# Board1.net
KiCad netlist of a schematic drawn in Altium Designer
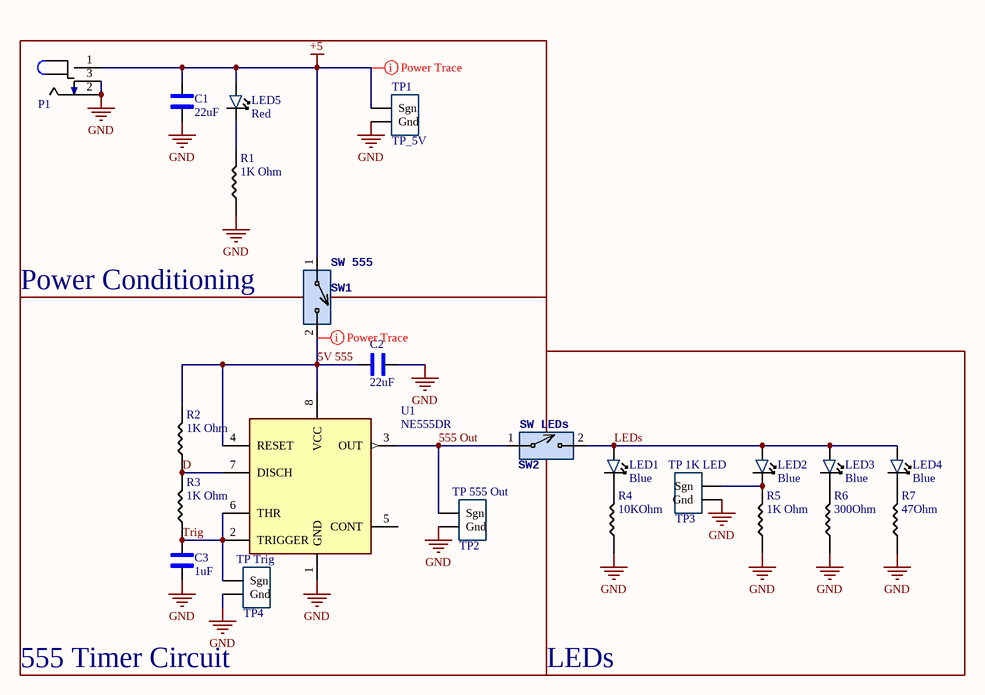
[diagram p0: Board1.SchDoc]

(export (version "E")
  (design (tool "Eeschema 10.0.6"))
  (components
    (comp (ref "C1")
      (value "22uF")
      (footprint "1206_Passive_Capacitor")
      (description "22uF ±10% 25V X5R 1206 Multilayer Ceramic Capacitors MLCC - SMD/SMT RoHS")
      (fields (field (name "MFR PART #") "CL31A226KAHNNNE") (field (name "LCSC PART#") "C12891"))
      (libsource (lib "ECEN5730Lib_2023_01_DS") (part "C_22uF_1206"))
    )
    (comp (ref "C2")
      (value "22uF")
      (footprint "1206_Passive_Capacitor")
      (description "22uF ±10% 25V X5R 1206 Multilayer Ceramic Capacitors MLCC - SMD/SMT RoHS")
      (fields (field (name "MFR PART #") "CL31A226KAHNNNE") (field (name "LCSC PART#") "C12891"))
      (libsource (lib "ECEN5730Lib_2023_01_DS") (part "C_22uF_1206"))
    )
    (comp (ref "C3")
      (value "1uF")
      (footprint "1206_Passive_Capacitor")
      (description "MULTILAYER CERAMIC CAPACITORS MLCC - SMD/SMT 1UF 50V 1206 ROHS")
      (fields (field (name "MFR PART #") "CL31B105KBHNNNE") (field (name "LCSC PART#") "C1848"))
      (libsource (lib "ECEN5730Lib_2023_01_DS") (part "C_1uF_1206"))
    )
    (comp (ref "LED1")
      (value "Blue")
      (footprint "LED_1206")
      (description "blue 1206  Light Emitting Diodes (LED) ROHS")
      (fields (field (name "MFR PART #") "NCD1206B1") (field (name "LCSC PART#") "C130717"))
      (libsource (lib "ECEN5730Lib_2023_01_DS") (part "LED_BLUE_1206"))
    )
    (comp (ref "LED2")
      (value "Blue")
      (footprint "LED_1206")
      (description "blue 1206  Light Emitting Diodes (LED) ROHS")
      (fields (field (name "MFR PART #") "NCD1206B1") (field (name "LCSC PART#") "C130717"))
      (libsource (lib "ECEN5730Lib_2023_01_DS") (part "LED_BLUE_1206"))
    )
    (comp (ref "LED3")
      (value "Blue")
      (footprint "LED_1206")
      (description "blue 1206  Light Emitting Diodes (LED) ROHS")
      (fields (field (name "MFR PART #") "NCD1206B1") (field (name "LCSC PART#") "C130717"))
      (libsource (lib "ECEN5730Lib_2023_01_DS") (part "LED_BLUE_1206"))
    )
    (comp (ref "LED4")
      (value "Blue")
      (footprint "LED_1206")
      (description "blue 1206  Light Emitting Diodes (LED) ROHS")
      (fields (field (name "MFR PART #") "NCD1206B1") (field (name "LCSC PART#") "C130717"))
      (libsource (lib "ECEN5730Lib_2023_01_DS") (part "LED_BLUE_1206"))
    )
    (comp (ref "LED5")
      (value "Red")
      (footprint "LED_1206")
      (description "Red 621~631nm 1206 Light Emitting Diodes (LED) RoHS")
      (fields (field (name "MFR PART #") "15-21/R6C-FQ1R1B/2T") (field (name "LCSC PART#") "C93133"))
      (libsource (lib "ECEN5730Lib_2023_01_DS") (part "LED_RED_1206"))
    )
    (comp (ref "P1")
      (value "Power Jack")
      (footprint "Power_Jack")
      (description "Power Barrel Connector Jack 2.10mm ID (0.083\"), 5.50mm OD (0.217\") Through Hole, Right Angle")
      (fields (field (name "MFR PART #") "PJ-102A") (field (name "LCSC PART#") "C136744"))
      (libsource (lib "ECEN5730Lib_2023_01_DS") (part "P_Power Jack"))
    )
    (comp (ref "R1")
      (value "1K Ohm")
      (footprint "1206_Passive_Resitor")
      (description "CHIP RESISTOR - SURFACE MOUNT 1KOHMS ±1% 1/4W 1206 ROHS")
      (fields (field (name "MFR PART #") "RNCP1206FTD1K00CT") (field (name "LCSC PART#") "C4410"))
      (libsource (lib "ECEN5730Lib_2023_01_DS") (part "R_1K_1206"))
    )
    (comp (ref "R2")
      (value "1K Ohm")
      (footprint "1206_Passive_Resitor")
      (description "CHIP RESISTOR - SURFACE MOUNT 1KOHMS ±1% 1/4W 1206 ROHS")
      (fields (field (name "MFR PART #") "RNCP1206FTD1K00CT") (field (name "LCSC PART#") "C4410"))
      (libsource (lib "ECEN5730Lib_2023_01_DS") (part "R_1K_1206"))
    )
    (comp (ref "R3")
      (value "1K Ohm")
      (footprint "1206_Passive_Resitor")
      (description "CHIP RESISTOR - SURFACE MOUNT 1KOHMS ±1% 1/4W 1206 ROHS")
      (fields (field (name "MFR PART #") "RNCP1206FTD1K00CT") (field (name "LCSC PART#") "C4410"))
      (libsource (lib "ECEN5730Lib_2023_01_DS") (part "R_1K_1206"))
    )
    (comp (ref "R4")
      (value "10KOhm")
      (footprint "1206_Passive_Resitor")
      (description "10 kOhms ±5% 0.25W, 1/4W Chip Resistor 1206 (3216 Metric) Automotive AEC-Q200 Thick Film")
      (fields (field (name "MFR PART #") "RMCF1206FT10K0") (field (name "LCSC PART#") "C17902"))
      (libsource (lib "ECEN5730Lib_2023_01_DS") (part "R_10KOhm_1206"))
    )
    (comp (ref "R5")
      (value "1K Ohm")
      (footprint "1206_Passive_Resitor")
      (description "CHIP RESISTOR - SURFACE MOUNT 1KOHMS ±1% 1/4W 1206 ROHS")
      (fields (field (name "MFR PART #") "RNCP1206FTD1K00CT") (field (name "LCSC PART#") "C4410"))
      (libsource (lib "ECEN5730Lib_2023_01_DS") (part "R_1K_1206"))
    )
    (comp (ref "R6")
      (value "300Ohm")
      (footprint "1206_Passive_Resitor")
      (description "CHIP RESISTOR - SURFACE MOUNT 300OHMS ±1% 1/4W 1206 ROHS")
      (fields (field (name "MFR PART #") "1206W4F3000T5E") (field (name "LCSC PART#") "C17887"))
      (libsource (lib "ECEN5730Lib_2023_01_DS") (part "R_300Ohm_1206"))
    )
    (comp (ref "R7")
      (value "47Ohm")
      (footprint "1206_Passive_Resitor")
      (description "47Ω ±5% 0.25W ±200ppm/℃ 1206 Chip Resistor - Surface Mount RoHS")
      (fields (field (name "MFR PART #") "1206W4J0470T5E") (field (name "LCSC PART#") "C25384"))
      (libsource (lib "ECEN5730Lib_2023_01_DS") (part "R_47Ohm_1206"))
    )
    (comp (ref "SW1")
      (value "SW 555")
      (footprint "2Pin-Header-Conn")
      (description "2Pin Header")
      (fields (field (name "LCSC PART#") "C124375"))
      (libsource (lib "ECEN5730Lib_2023_01_DS") (part "SW_2Pin_100mil_Switch"))
    )
    (comp (ref "SW2")
      (value "SW LEDs")
      (footprint "2Pin-Header-Conn")
      (description "2Pin Header")
      (fields (field (name "LCSC PART#") "C124375"))
      (libsource (lib "") (part "SW_2Pin_100mil_Switch_1"))
    )
    (comp (ref "TP1")
      (value "TP_5V")
      (footprint "TP10x_Probe")
      (description "Test Point 300 mil centers")
      (libsource (lib "ECEN5730Lib_2023_01_DS") (part "TP_10x_Probe"))
    )
    (comp (ref "TP2")
      (value "TP 555 Out")
      (footprint "TP10x_Probe")
      (description "Test Point 300 mil centers")
      (libsource (lib "ECEN5730Lib_2023_01_DS") (part "TP_10x_Probe"))
    )
    (comp (ref "TP3")
      (value "TP 1K LED")
      (footprint "TP10x_Probe")
      (description "Test Point 300 mil centers")
      (libsource (lib "") (part "TP_10x_Probe_1"))
    )
    (comp (ref "TP4")
      (value "TP Trig")
      (footprint "TP10x_Probe")
      (description "Test Point 300 mil centers")
      (libsource (lib "ECEN5730Lib_2023_01_DS") (part "TP_10x_Probe"))
    )
    (comp (ref "U1")
      (value "NE555DR")
      (footprint "TS555IDTTR")
      (description "555 Timer SOIC-8_150MIL ROHS 150ns Rise Time")
      (fields (field (name "LCSC PART#") "C7593"))
      (libsource (lib "ECEN5730Lib_2023_01_DS") (part "U_555_Slow"))
    )
  )
  (nets
    (net (code "1") (name "+5") (class "Default")
      (node (ref "C1") (pin "2") (pinfunction "2_2") (pintype "passive"))
      (node (ref "LED5") (pin "1") (pinfunction "1_1") (pintype "passive"))
      (node (ref "P1") (pin "1") (pinfunction "1_1") (pintype "power_in"))
      (node (ref "SW1") (pin "1") (pinfunction "1_1") (pintype "passive"))
      (node (ref "TP1") (pin "1") (pinfunction "Sgn_1") (pintype "passive"))
    )
    (net (code "2") (name "/5V 555") (class "Default")
      (node (ref "C2") (pin "2") (pinfunction "2_2") (pintype "passive"))
      (node (ref "R2") (pin "2") (pinfunction "2_2") (pintype "passive"))
      (node (ref "SW1") (pin "2") (pinfunction "2_2") (pintype "passive"))
      (node (ref "U1") (pin "4") (pinfunction "RESET_4") (pintype "passive"))
      (node (ref "U1") (pin "8") (pinfunction "VCC_8") (pintype "power_in"))
    )
    (net (code "3") (name "/555 Out") (class "Default")
      (node (ref "SW2") (pin "1") (pinfunction "1_1") (pintype "passive"))
      (node (ref "TP2") (pin "1") (pinfunction "Sgn_1") (pintype "passive"))
      (node (ref "U1") (pin "3") (pinfunction "OUT_3") (pintype "output"))
    )
    (net (code "4") (name "/D") (class "Default")
      (node (ref "R2") (pin "1") (pinfunction "1_1") (pintype "passive"))
      (node (ref "R3") (pin "2") (pinfunction "2_2") (pintype "passive"))
      (node (ref "U1") (pin "7") (pinfunction "DISCH_7") (pintype "passive"))
    )
    (net (code "5") (name "/LEDs") (class "Default")
      (node (ref "LED1") (pin "1") (pinfunction "1_1") (pintype "passive"))
      (node (ref "LED2") (pin "1") (pinfunction "1_1") (pintype "passive"))
      (node (ref "LED3") (pin "1") (pinfunction "1_1") (pintype "passive"))
      (node (ref "LED4") (pin "1") (pinfunction "1_1") (pintype "passive"))
      (node (ref "SW2") (pin "2") (pinfunction "2_2") (pintype "passive"))
    )
    (net (code "6") (name "/Trig") (class "Default")
      (node (ref "C3") (pin "2") (pinfunction "2_2") (pintype "passive"))
      (node (ref "R3") (pin "1") (pinfunction "1_1") (pintype "passive"))
      (node (ref "TP4") (pin "1") (pinfunction "Sgn_1") (pintype "passive"))
      (node (ref "U1") (pin "2") (pinfunction "TRIGGER_2") (pintype "passive"))
      (node (ref "U1") (pin "6") (pinfunction "THR_6") (pintype "passive"))
    )
    (net (code "7") (name "GND") (class "Default")
      (node (ref "C1") (pin "1") (pinfunction "1_1") (pintype "passive"))
      (node (ref "C2") (pin "1") (pinfunction "1_1") (pintype "passive"))
      (node (ref "C3") (pin "1") (pinfunction "1_1") (pintype "passive"))
      (node (ref "P1") (pin "2") (pinfunction "2_2") (pintype "power_in"))
      (node (ref "P1") (pin "3") (pinfunction "3_3") (pintype "power_in"))
      (node (ref "R1") (pin "1") (pinfunction "1_1") (pintype "passive"))
      (node (ref "R4") (pin "1") (pinfunction "1_1") (pintype "passive"))
      (node (ref "R5") (pin "1") (pinfunction "1_1") (pintype "passive"))
      (node (ref "R6") (pin "1") (pinfunction "1_1") (pintype "passive"))
      (node (ref "R7") (pin "1") (pinfunction "1_1") (pintype "passive"))
      (node (ref "TP1") (pin "2") (pinfunction "Gnd_2") (pintype "passive"))
      (node (ref "TP2") (pin "2") (pinfunction "Gnd_2") (pintype "passive"))
      (node (ref "TP3") (pin "2") (pinfunction "Gnd_2") (pintype "passive"))
      (node (ref "TP4") (pin "2") (pinfunction "Gnd_2") (pintype "passive"))
      (node (ref "U1") (pin "1") (pinfunction "GND_1") (pintype "power_in"))
    )
    (net (code "8") (name "Net-(LED1-Pad2)") (class "Default")
      (node (ref "LED1") (pin "2") (pinfunction "2_2") (pintype "passive"))
      (node (ref "R4") (pin "2") (pinfunction "2_2") (pintype "passive"))
    )
    (net (code "9") (name "Net-(LED3-Pad2)") (class "Default")
      (node (ref "LED3") (pin "2") (pinfunction "2_2") (pintype "passive"))
      (node (ref "R6") (pin "2") (pinfunction "2_2") (pintype "passive"))
    )
    (net (code "10") (name "Net-(LED4-Pad2)") (class "Default")
      (node (ref "LED4") (pin "2") (pinfunction "2_2") (pintype "passive"))
      (node (ref "R7") (pin "2") (pinfunction "2_2") (pintype "passive"))
    )
    (net (code "11") (name "Net-(LED5-Pad2)") (class "Default")
      (node (ref "LED5") (pin "2") (pinfunction "2_2") (pintype "passive"))
      (node (ref "R1") (pin "2") (pinfunction "2_2") (pintype "passive"))
    )
    (net (code "12") (name "Net-(TP3-Sgn)") (class "Default")
      (node (ref "LED2") (pin "2") (pinfunction "2_2") (pintype "passive"))
      (node (ref "R5") (pin "2") (pinfunction "2_2") (pintype "passive"))
      (node (ref "TP3") (pin "1") (pinfunction "Sgn_1") (pintype "passive"))
    )
    (net (code "13") (name "unconnected-(U1-CONT-Pad5)") (class "Default")
      (node (ref "U1") (pin "5") (pinfunction "CONT_5") (pintype "passive"))
    )
  )
)
